# User_LEDs.net
KiCad netlist of a schematic drawn in Altium Designer
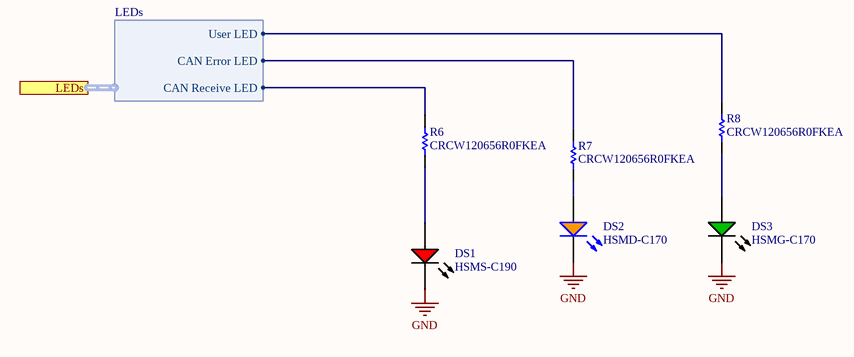
[diagram p0: User_LEDs.SchDoc]

(export (version "E")
  (design (tool "Eeschema 10.0.6"))
  (components
    (comp (ref "DS1")
      (value "HSMS-C190")
      (footprint "AVAG-HSMX-C190_V")
      (description "LED Uni-Color Red, 52 mW, 20 mA, -40 to 85 degC, 2-Pin SMD, RoHS, Tape and Reel")
      (fields (field (name "MANUFACTURER") "Avago"))
      (libsource (lib "Altium Content Vault") (part "LED-RED-AK-2"))
    )
    (comp (ref "DS2")
      (value "HSMD-C170")
      (footprint "AVAG-HSMX-C170_V")
      (description "LED Uni-Color Orange, 52 mW, 20 mA, -40 to 85 degC, 2-Pin SMD, RoHS, Tape and Reel")
      (fields (field (name "MANUFACTURER") "Avago"))
      (libsource (lib "Altium Content Vault") (part "LED-ORANGE-AK-2"))
    )
    (comp (ref "DS3")
      (value "HSMG-C170")
      (footprint "AVAG-HSMX-C170_V")
      (description "Chip LED, Green, 2.2 V, -40 to 85 degC, 2-Pin SMD, Pb-Free, Tape and Reel")
      (fields (field (name "MANUFACTURER") "Avago"))
      (libsource (lib "Altium Content Vault") (part "LED_GREEN_A1K2-2"))
    )
    (comp (ref "R6")
      (value "CRCW120656R0FKEA")
      (footprint "RESC3216X60X45LL10T20")
      (fields (field (name "MANUFACTURER") "Vishay Dale"))
      (libsource (lib "Altium Content Vault") (part "RES"))
    )
    (comp (ref "R7")
      (value "CRCW120656R0FKEA")
      (footprint "RESC3216X60X45LL10T20")
      (fields (field (name "MANUFACTURER") "Vishay Dale"))
      (libsource (lib "Altium Content Vault") (part "RES"))
    )
    (comp (ref "R8")
      (value "CRCW120656R0FKEA")
      (footprint "RESC3216X60X45LL10T20")
      (fields (field (name "MANUFACTURER") "Vishay Dale"))
      (libsource (lib "Altium Content Vault") (part "RES"))
    )
  )
  (nets
    (net (code "2") (name "/CAN Error LED") (class "Default")
      (node (ref "R7") (pin "2") (pinfunction "2_2") (pintype "passive"))
    )
    (net (code "3") (name "/CAN Receive LED") (class "Default")
      (node (ref "R6") (pin "2") (pinfunction "2_2") (pintype "passive"))
    )
    (net (code "4") (name "/User LED") (class "Default")
      (node (ref "R8") (pin "2") (pinfunction "2_2") (pintype "passive"))
    )
    (net (code "6") (name "GND") (class "Default")
      (node (ref "DS1") (pin "2") (pinfunction "K_2") (pintype "passive"))
      (node (ref "DS2") (pin "2") (pinfunction "K_2") (pintype "passive"))
      (node (ref "DS3") (pin "2") (pinfunction "K_2") (pintype "passive"))
    )
    (net (code "7") (name "Net-(DS1-A)") (class "Default")
      (node (ref "DS1") (pin "1") (pinfunction "A_1") (pintype "passive"))
      (node (ref "R6") (pin "1") (pinfunction "1_1") (pintype "passive"))
    )
    (net (code "8") (name "Net-(DS2-A)") (class "Default")
      (node (ref "DS2") (pin "1") (pinfunction "A_1") (pintype "passive"))
      (node (ref "R7") (pin "1") (pinfunction "1_1") (pintype "passive"))
    )
    (net (code "9") (name "Net-(DS3-A)") (class "Default")
      (node (ref "DS3") (pin "1") (pinfunction "A_1") (pintype "passive"))
      (node (ref "R8") (pin "1") (pinfunction "1_1") (pintype "passive"))
    )
  )
)
